# BatteryPowerModule_Relay.net
KiCad netlist of a schematic drawn in EasyEDA
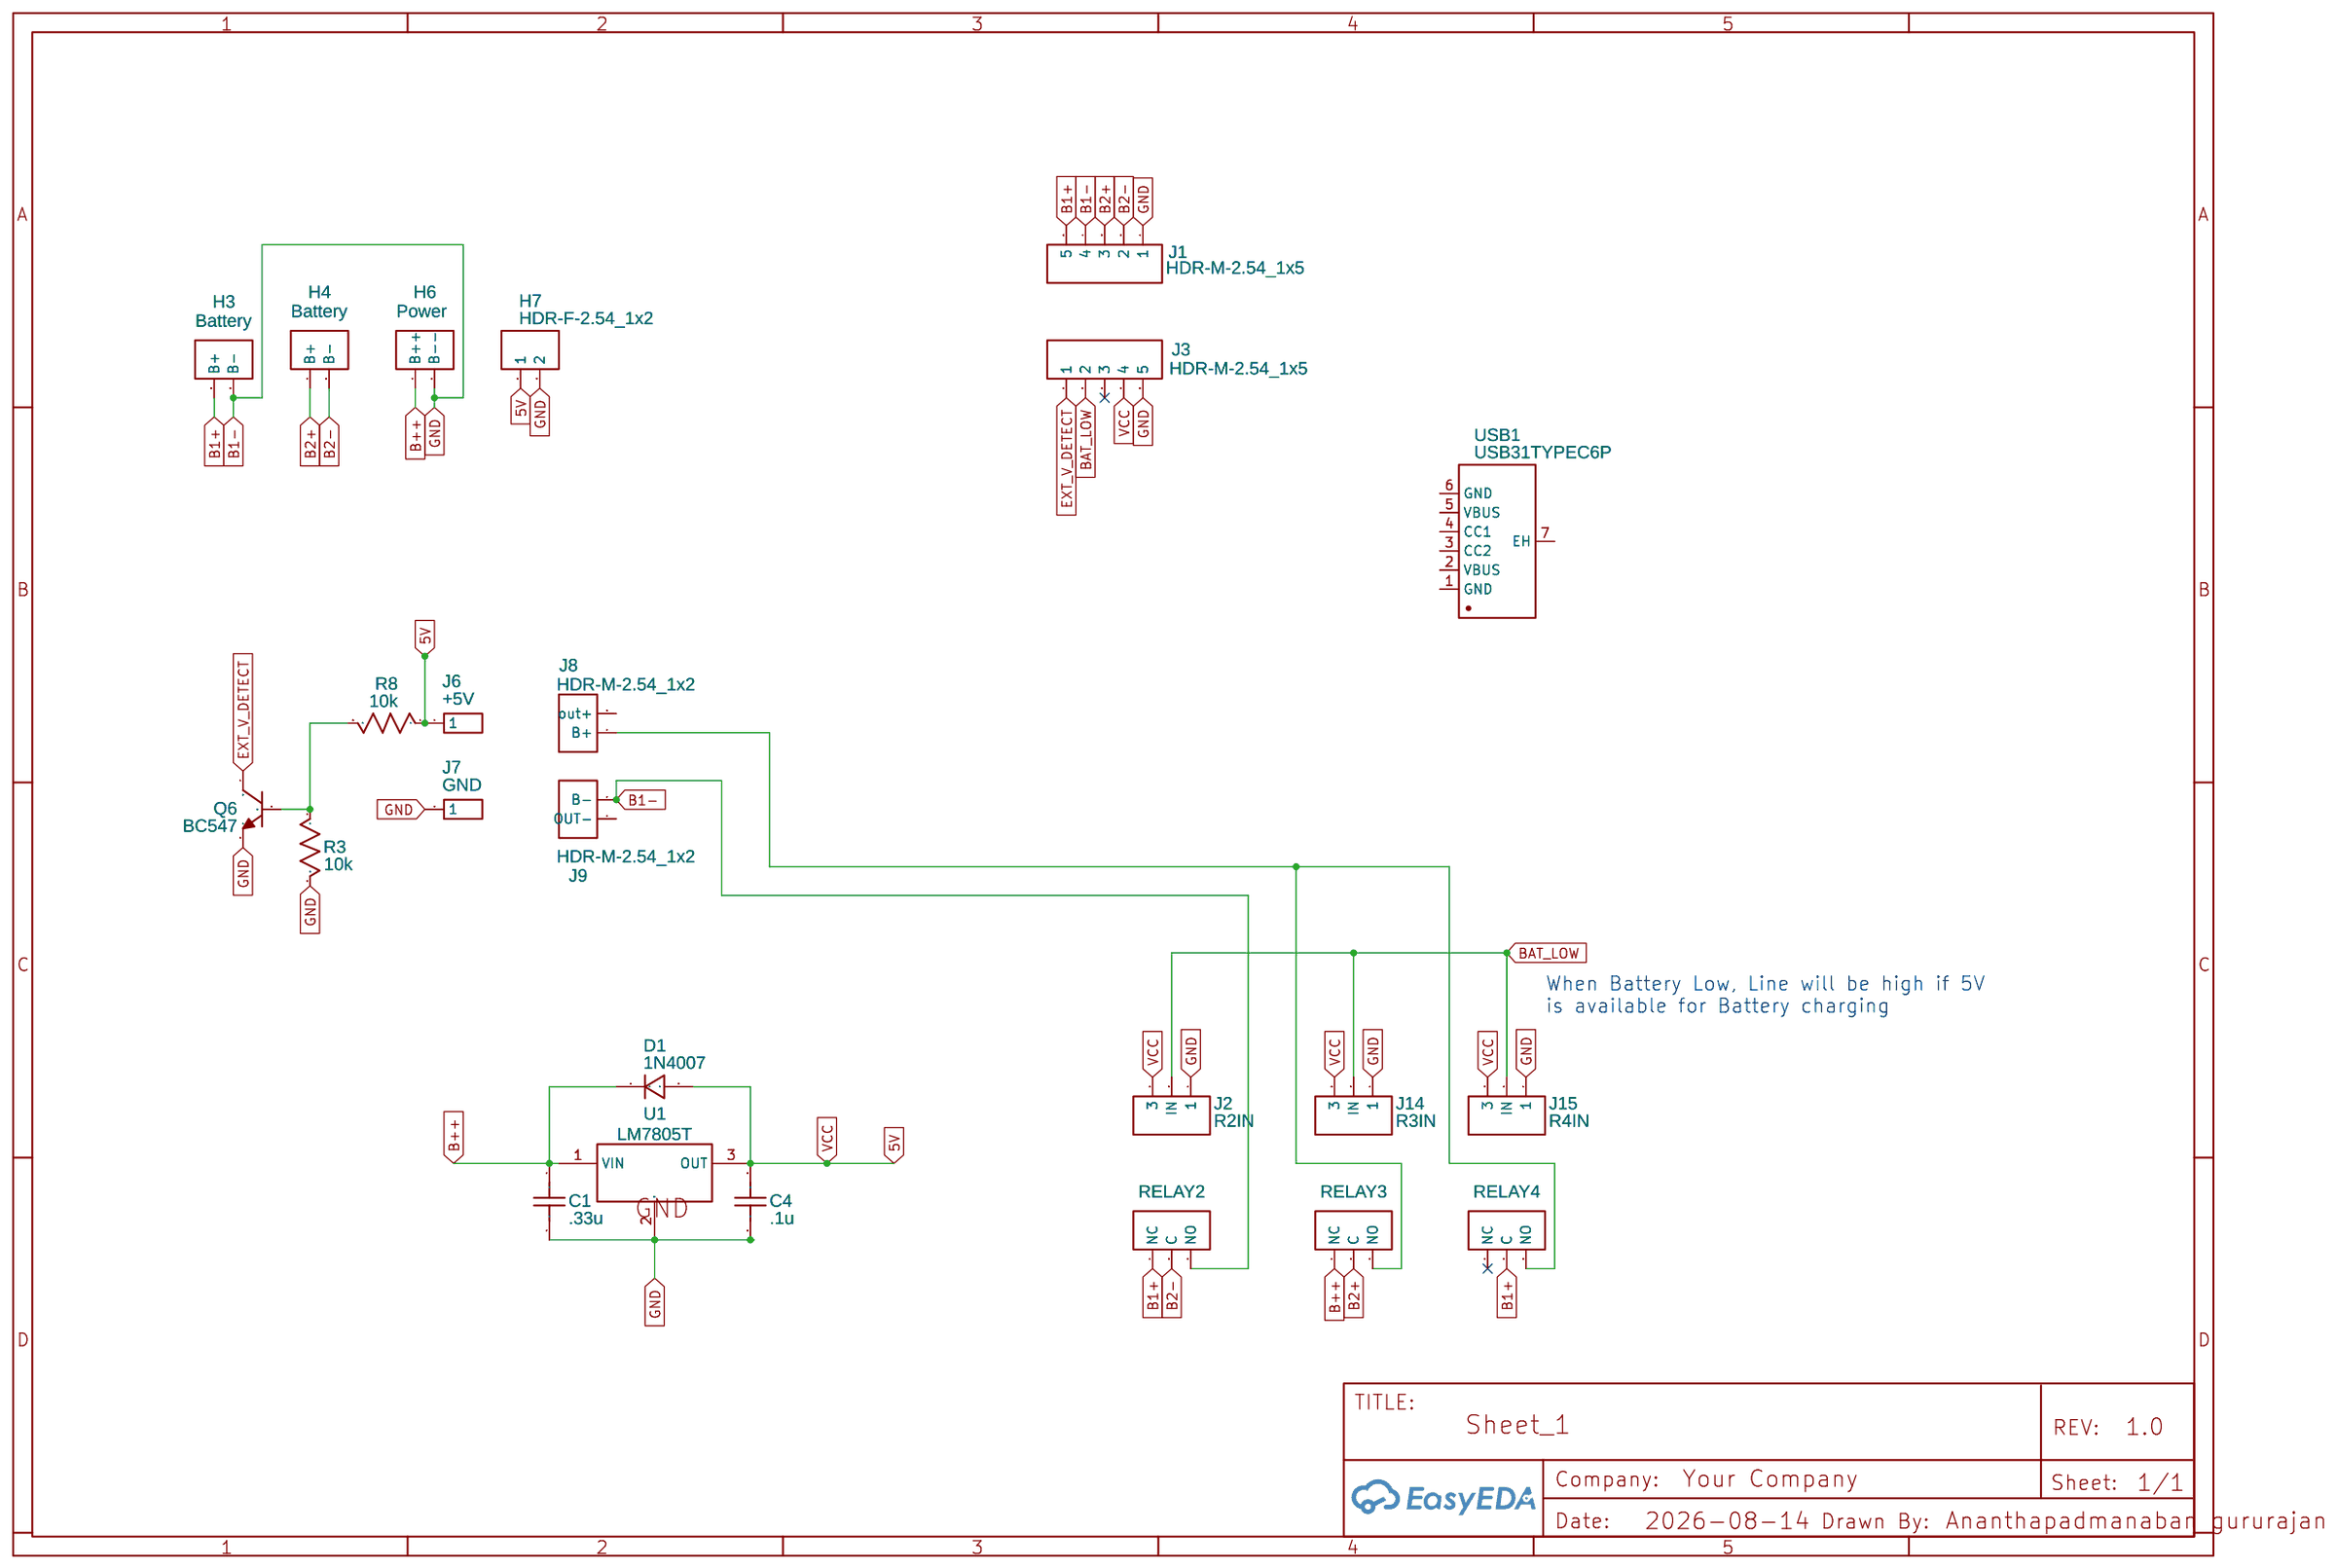
[diagram p0: schematic sheet]

(export (version "E")
  (design (tool "Eeschema 10.0.6"))
  (components
    (comp (ref "C1") (value ".33u") (libsource (lib "") (part "C_RAD-0.1_US")))
    (comp (ref "C4") (value ".1u") (libsource (lib "") (part "C_RAD-0.1_US")))
    (comp (ref "D1")
      (value "1N4007")
      (fields (field (name "Manufacturer") "SEMTECH"))
      (libsource (lib "") (part "1N4007"))
    )
    (comp (ref "H3") (value "Battery") (libsource (lib "") (part "HDR-F-2.54_1x2_1")))
    (comp (ref "H4") (value "Battery") (libsource (lib "") (part "HDR-F-2.54_1x2_1")))
    (comp (ref "H6") (value "Power") (libsource (lib "") (part "HDR-F-2.54_1x2_2")))
    (comp (ref "H7") (value "HDR-F-2.54_1x2") (libsource (lib "") (part "HDR-F-2.54_1x2")))
    (comp (ref "J1") (value "HDR-M-2.54_1x5") (libsource (lib "") (part "HDR-M-2.54_1x5")))
    (comp (ref "J2") (value "R2IN") (libsource (lib "") (part "HDR-M-2.54_1x3")))
    (comp (ref "J3") (value "HDR-M-2.54_1x5") (libsource (lib "") (part "HDR-M-2.54_1x5_1")))
    (comp (ref "J6") (value "+5V") (libsource (lib "") (part "HDR-M-2.54_1x1")))
    (comp (ref "J7") (value "GND") (libsource (lib "") (part "HDR-M-2.54_1x1")))
    (comp (ref "J8") (value "HDR-M-2.54_1x2") (libsource (lib "") (part "HDR-M-2.54_1x2_1")))
    (comp (ref "J9") (value "HDR-M-2.54_1x2") (libsource (lib "") (part "HDR-M-2.54_1x2")))
    (comp (ref "J14") (value "R3IN") (libsource (lib "") (part "HDR-M-2.54_1x3")))
    (comp (ref "J15") (value "R4IN") (libsource (lib "") (part "HDR-M-2.54_1x3")))
    (comp (ref "Q6")
      (value "BC547")
      (fields
        (field (name "Manufacturer Part") "BC547(RANGE:420-800)")
        (field (name "Manufacturer") "CJ(江苏长电/长晶)")
      )
      (libsource (lib "") (part "BC547"))
    )
    (comp (ref "R3") (value "10k") (libsource (lib "") (part "R_AXIAL-0.3_US_1")))
    (comp (ref "R8") (value "10k") (libsource (lib "") (part "R_AXIAL-0.3_US")))
    (comp (ref "RELAY2") (value "Relay1") (libsource (lib "") (part "HDR-M-2.54_1x3_1")))
    (comp (ref "RELAY3") (value "Relay1") (libsource (lib "") (part "HDR-M-2.54_1x3_1")))
    (comp (ref "RELAY4") (value "Relay1") (libsource (lib "") (part "HDR-M-2.54_1x3_1")))
    (comp (ref "U1")
      (value "LM7805T")
      (fields (field (name "Manufacturer") "HGC(华冠)"))
      (libsource (lib "") (part "LM7805T"))
    )
    (comp (ref "USB1") (value "USB31TYPEC6P") (libsource (lib "") (part "USB31TYPEC6P")))
  )
  (nets
    (net (code "1") (name "5V") (class "Default")
      (node (ref "C4") (pin "1") (pinfunction "1_1") (pintype "unspecified"))
      (node (ref "D1") (pin "2") (pinfunction "2_2") (pintype "unspecified"))
      (node (ref "H7") (pin "1") (pinfunction "1_1") (pintype "input"))
      (node (ref "J14") (pin "3") (pinfunction "3_3") (pintype "input"))
      (node (ref "J15") (pin "3") (pinfunction "3_3") (pintype "input"))
      (node (ref "J2") (pin "3") (pinfunction "3_3") (pintype "input"))
      (node (ref "J3") (pin "4") (pinfunction "4_4") (pintype "unspecified"))
      (node (ref "J6") (pin "1") (pinfunction "1_1") (pintype "input"))
      (node (ref "R8") (pin "1") (pinfunction "1_1") (pintype "unspecified"))
      (node (ref "U1") (pin "3") (pinfunction "OUT_3") (pintype "passive"))
    )
    (net (code "2") (name "B++") (class "Default")
      (node (ref "C1") (pin "1") (pinfunction "1_1") (pintype "unspecified"))
      (node (ref "D1") (pin "1") (pinfunction "1_1") (pintype "unspecified"))
      (node (ref "H6") (pin "1") (pinfunction "B++_1") (pintype "input"))
      (node (ref "RELAY3") (pin "1") (pinfunction "NC_1") (pintype "input"))
      (node (ref "U1") (pin "1") (pinfunction "VIN_1") (pintype "passive"))
    )
    (net (code "3") (name "B1+") (class "Default")
      (node (ref "H3") (pin "1") (pinfunction "B+_1") (pintype "input"))
      (node (ref "J1") (pin "5") (pinfunction "5_5") (pintype "unspecified"))
      (node (ref "RELAY2") (pin "1") (pinfunction "NC_1") (pintype "input"))
      (node (ref "RELAY4") (pin "2") (pinfunction "C_2") (pintype "input"))
    )
    (net (code "4") (name "B1-") (class "Default")
      (node (ref "C1") (pin "2") (pinfunction "2_2") (pintype "unspecified"))
      (node (ref "C4") (pin "2") (pinfunction "2_2") (pintype "unspecified"))
      (node (ref "H3") (pin "2") (pinfunction "B-_2") (pintype "input"))
      (node (ref "H6") (pin "2") (pinfunction "B--_2") (pintype "input"))
      (node (ref "H7") (pin "2") (pinfunction "2_2") (pintype "input"))
      (node (ref "J1") (pin "1") (pinfunction "1_1") (pintype "unspecified"))
      (node (ref "J1") (pin "4") (pinfunction "4_4") (pintype "unspecified"))
      (node (ref "J14") (pin "1") (pinfunction "1_1") (pintype "input"))
      (node (ref "J15") (pin "1") (pinfunction "1_1") (pintype "input"))
      (node (ref "J2") (pin "1") (pinfunction "1_1") (pintype "input"))
      (node (ref "J3") (pin "5") (pinfunction "5_5") (pintype "unspecified"))
      (node (ref "J7") (pin "1") (pinfunction "1_1") (pintype "input"))
      (node (ref "J9") (pin "2") (pinfunction "B-_2") (pintype "unspecified"))
      (node (ref "Q6") (pin "3") (pinfunction "E_3") (pintype "unspecified"))
      (node (ref "R3") (pin "2") (pinfunction "2_2") (pintype "unspecified"))
      (node (ref "RELAY2") (pin "3") (pinfunction "NO_3") (pintype "input"))
      (node (ref "U1") (pin "2") (pinfunction "GND_2") (pintype "passive"))
    )
    (net (code "5") (name "B2+") (class "Default")
      (node (ref "H4") (pin "1") (pinfunction "B+_1") (pintype "input"))
      (node (ref "J1") (pin "3") (pinfunction "3_3") (pintype "unspecified"))
      (node (ref "RELAY3") (pin "2") (pinfunction "C_2") (pintype "input"))
    )
    (net (code "6") (name "B2-") (class "Default")
      (node (ref "H4") (pin "2") (pinfunction "B-_2") (pintype "input"))
      (node (ref "J1") (pin "2") (pinfunction "2_2") (pintype "unspecified"))
      (node (ref "RELAY2") (pin "2") (pinfunction "C_2") (pintype "input"))
    )
    (net (code "7") (name "BAT_LOW") (class "Default")
      (node (ref "J14") (pin "2") (pinfunction "IN_2") (pintype "input"))
      (node (ref "J15") (pin "2") (pinfunction "IN_2") (pintype "input"))
      (node (ref "J2") (pin "2") (pinfunction "IN_2") (pintype "input"))
      (node (ref "J3") (pin "2") (pinfunction "2_2") (pintype "unspecified"))
    )
    (net (code "8") (name "EXT_V_DETECT") (class "Default")
      (node (ref "J3") (pin "1") (pinfunction "1_1") (pintype "unspecified"))
      (node (ref "Q6") (pin "1") (pinfunction "C_1") (pintype "unspecified"))
    )
    (net (code "9") (name "Net-(J8-B+)") (class "Default")
      (node (ref "J8") (pin "1") (pinfunction "B+_1") (pintype "unspecified"))
      (node (ref "RELAY3") (pin "3") (pinfunction "NO_3") (pintype "input"))
      (node (ref "RELAY4") (pin "3") (pinfunction "NO_3") (pintype "input"))
    )
    (net (code "10") (name "Net-(Q6-B)") (class "Default")
      (node (ref "Q6") (pin "2") (pinfunction "B_2") (pintype "unspecified"))
      (node (ref "R3") (pin "1") (pinfunction "1_1") (pintype "unspecified"))
      (node (ref "R8") (pin "2") (pinfunction "2_2") (pintype "unspecified"))
    )
    (net (code "11") (name "unconnected-(J3-Pad3)") (class "Default")
      (node (ref "J3") (pin "3") (pinfunction "3_3") (pintype "unspecified+no_connect"))
    )
    (net (code "12") (name "unconnected-(J8-out+-Pad2)") (class "Default")
      (node (ref "J8") (pin "2") (pinfunction "out+_2") (pintype "unspecified"))
    )
    (net (code "13") (name "unconnected-(J9-OUT--Pad1)") (class "Default")
      (node (ref "J9") (pin "1") (pinfunction "OUT-_1") (pintype "unspecified"))
    )
    (net (code "14") (name "unconnected-(RELAY4-NC-Pad1)") (class "Default")
      (node (ref "RELAY4") (pin "1") (pinfunction "NC_1") (pintype "input+no_connect"))
    )
    (net (code "15") (name "unconnected-(USB1-CC1-Pad4)") (class "Default")
      (node (ref "USB1") (pin "4") (pinfunction "CC1_4") (pintype "unspecified"))
    )
    (net (code "16") (name "unconnected-(USB1-CC2-Pad3)") (class "Default")
      (node (ref "USB1") (pin "3") (pinfunction "CC2_3") (pintype "unspecified"))
    )
    (net (code "17") (name "unconnected-(USB1-EH-Pad7)") (class "Default")
      (node (ref "USB1") (pin "7") (pinfunction "EH_7") (pintype "unspecified"))
    )
    (net (code "18") (name "unconnected-(USB1-GND-Pad1)") (class "Default")
      (node (ref "USB1") (pin "1") (pinfunction "GND_1") (pintype "unspecified"))
    )
    (net (code "19") (name "unconnected-(USB1-GND-Pad6)") (class "Default")
      (node (ref "USB1") (pin "6") (pinfunction "GND_6") (pintype "unspecified"))
    )
    (net (code "20") (name "unconnected-(USB1-VBUS-Pad2)") (class "Default")
      (node (ref "USB1") (pin "2") (pinfunction "VBUS_2") (pintype "unspecified"))
    )
    (net (code "21") (name "unconnected-(USB1-VBUS-Pad5)") (class "Default")
      (node (ref "USB1") (pin "5") (pinfunction "VBUS_5") (pintype "unspecified"))
    )
  )
)
